# Kammsensor.net
KiCad netlist of a schematic drawn in EAGLE
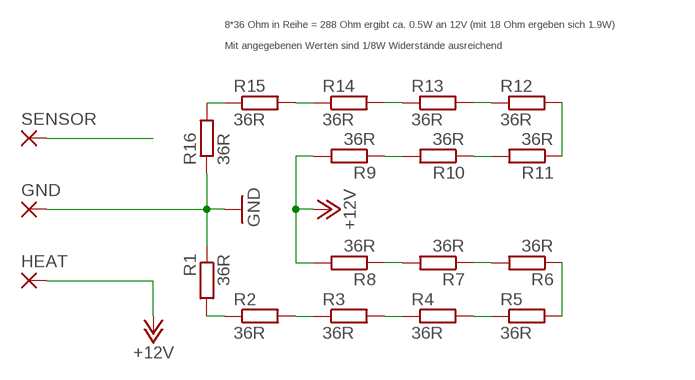
[diagram p0: schematic, sheet 1]

(export (version "E")
  (design (tool "Eeschema 10.0.6"))
  (components
    (comp (ref "GND")
      (value "WIREPADSMD5-1,8")
      (footprint "eagle-import:5-1,8")
      (libsource (lib "eagle-import") (part "WIREPADSMD5-1,8"))
    )
    (comp (ref "HEAT")
      (value "WIREPADSMD5-1,8")
      (footprint "eagle-import:5-1,8")
      (libsource (lib "eagle-import") (part "WIREPADSMD5-1,8"))
    )
    (comp (ref "R1")
      (value "36R")
      (footprint "eagle-import:M1206")
      (libsource (lib "eagle-import") (part "R-EU_M1206"))
    )
    (comp (ref "R2")
      (value "36R")
      (footprint "eagle-import:M1206")
      (libsource (lib "eagle-import") (part "R-EU_M1206"))
    )
    (comp (ref "R3")
      (value "36R")
      (footprint "eagle-import:M1206")
      (libsource (lib "eagle-import") (part "R-EU_M1206"))
    )
    (comp (ref "R4")
      (value "36R")
      (footprint "eagle-import:M1206")
      (libsource (lib "eagle-import") (part "R-EU_M1206"))
    )
    (comp (ref "R5")
      (value "36R")
      (footprint "eagle-import:M1206")
      (libsource (lib "eagle-import") (part "R-EU_M1206"))
    )
    (comp (ref "R6")
      (value "36R")
      (footprint "eagle-import:M1206")
      (libsource (lib "eagle-import") (part "R-EU_M1206"))
    )
    (comp (ref "R7")
      (value "36R")
      (footprint "eagle-import:M1206")
      (libsource (lib "eagle-import") (part "R-EU_M1206"))
    )
    (comp (ref "R8")
      (value "36R")
      (footprint "eagle-import:M1206")
      (libsource (lib "eagle-import") (part "R-EU_M1206"))
    )
    (comp (ref "R9")
      (value "36R")
      (footprint "eagle-import:M1206")
      (libsource (lib "eagle-import") (part "R-EU_M1206"))
    )
    (comp (ref "R10")
      (value "36R")
      (footprint "eagle-import:M1206")
      (libsource (lib "eagle-import") (part "R-EU_M1206"))
    )
    (comp (ref "R11")
      (value "36R")
      (footprint "eagle-import:M1206")
      (libsource (lib "eagle-import") (part "R-EU_M1206"))
    )
    (comp (ref "R12")
      (value "36R")
      (footprint "eagle-import:M1206")
      (libsource (lib "eagle-import") (part "R-EU_M1206"))
    )
    (comp (ref "R13")
      (value "36R")
      (footprint "eagle-import:M1206")
      (libsource (lib "eagle-import") (part "R-EU_M1206"))
    )
    (comp (ref "R14")
      (value "36R")
      (footprint "eagle-import:M1206")
      (libsource (lib "eagle-import") (part "R-EU_M1206"))
    )
    (comp (ref "R15")
      (value "36R")
      (footprint "eagle-import:M1206")
      (libsource (lib "eagle-import") (part "R-EU_M1206"))
    )
    (comp (ref "R16")
      (value "36R")
      (footprint "eagle-import:M1206")
      (libsource (lib "eagle-import") (part "R-EU_M1206"))
    )
    (comp (ref "SENSOR")
      (value "WIREPADSMD5-1,8")
      (footprint "eagle-import:5-1,8")
      (libsource (lib "eagle-import") (part "WIREPADSMD5-1,8"))
    )
  )
  (nets
    (net (code "1") (name "+12V") (class "Default")
      (node (ref "HEAT") (pin "1") (pinfunction "P_1") (pintype "passive"))
      (node (ref "R8") (pin "2") (pinfunction "2_2") (pintype "passive"))
      (node (ref "R9") (pin "2") (pinfunction "2_2") (pintype "passive"))
    )
    (net (code "2") (name "GND") (class "Default")
      (node (ref "GND") (pin "1") (pinfunction "P_1") (pintype "passive"))
      (node (ref "R1") (pin "1") (pinfunction "1_1") (pintype "passive"))
      (node (ref "R16") (pin "1") (pinfunction "1_1") (pintype "passive"))
    )
    (net (code "3") (name "Net-(R1-Pad2)") (class "Default")
      (node (ref "R1") (pin "2") (pinfunction "2_2") (pintype "passive"))
      (node (ref "R2") (pin "1") (pinfunction "1_1") (pintype "passive"))
    )
    (net (code "4") (name "Net-(R2-Pad2)") (class "Default")
      (node (ref "R2") (pin "2") (pinfunction "2_2") (pintype "passive"))
      (node (ref "R3") (pin "1") (pinfunction "1_1") (pintype "passive"))
    )
    (net (code "5") (name "Net-(R3-Pad2)") (class "Default")
      (node (ref "R3") (pin "2") (pinfunction "2_2") (pintype "passive"))
      (node (ref "R4") (pin "1") (pinfunction "1_1") (pintype "passive"))
    )
    (net (code "6") (name "Net-(R4-Pad2)") (class "Default")
      (node (ref "R4") (pin "2") (pinfunction "2_2") (pintype "passive"))
      (node (ref "R5") (pin "1") (pinfunction "1_1") (pintype "passive"))
    )
    (net (code "7") (name "Net-(R5-Pad2)") (class "Default")
      (node (ref "R5") (pin "2") (pinfunction "2_2") (pintype "passive"))
      (node (ref "R6") (pin "1") (pinfunction "1_1") (pintype "passive"))
    )
    (net (code "8") (name "Net-(R6-Pad2)") (class "Default")
      (node (ref "R6") (pin "2") (pinfunction "2_2") (pintype "passive"))
      (node (ref "R7") (pin "1") (pinfunction "1_1") (pintype "passive"))
    )
    (net (code "9") (name "Net-(R7-Pad2)") (class "Default")
      (node (ref "R7") (pin "2") (pinfunction "2_2") (pintype "passive"))
      (node (ref "R8") (pin "1") (pinfunction "1_1") (pintype "passive"))
    )
    (net (code "10") (name "Net-(R10-Pad1)") (class "Default")
      (node (ref "R10") (pin "1") (pinfunction "1_1") (pintype "passive"))
      (node (ref "R11") (pin "2") (pinfunction "2_2") (pintype "passive"))
    )
    (net (code "11") (name "Net-(R10-Pad2)") (class "Default")
      (node (ref "R10") (pin "2") (pinfunction "2_2") (pintype "passive"))
      (node (ref "R9") (pin "1") (pinfunction "1_1") (pintype "passive"))
    )
    (net (code "12") (name "Net-(R11-Pad1)") (class "Default")
      (node (ref "R11") (pin "1") (pinfunction "1_1") (pintype "passive"))
      (node (ref "R12") (pin "2") (pinfunction "2_2") (pintype "passive"))
    )
    (net (code "13") (name "Net-(R12-Pad1)") (class "Default")
      (node (ref "R12") (pin "1") (pinfunction "1_1") (pintype "passive"))
      (node (ref "R13") (pin "2") (pinfunction "2_2") (pintype "passive"))
    )
    (net (code "14") (name "Net-(R13-Pad1)") (class "Default")
      (node (ref "R13") (pin "1") (pinfunction "1_1") (pintype "passive"))
      (node (ref "R14") (pin "2") (pinfunction "2_2") (pintype "passive"))
    )
    (net (code "15") (name "Net-(R14-Pad1)") (class "Default")
      (node (ref "R14") (pin "1") (pinfunction "1_1") (pintype "passive"))
      (node (ref "R15") (pin "2") (pinfunction "2_2") (pintype "passive"))
    )
    (net (code "16") (name "Net-(R15-Pad1)") (class "Default")
      (node (ref "R15") (pin "1") (pinfunction "1_1") (pintype "passive"))
      (node (ref "R16") (pin "2") (pinfunction "2_2") (pintype "passive"))
    )
    (net (code "17") (name "unconnected-(SENSOR-P-Pad1)") (class "Default")
      (node (ref "SENSOR") (pin "1") (pinfunction "P_1") (pintype "passive"))
    )
  )
)
